# senseBox-RTC-RV8523_v20.net
KiCad netlist of a schematic drawn in EAGLE
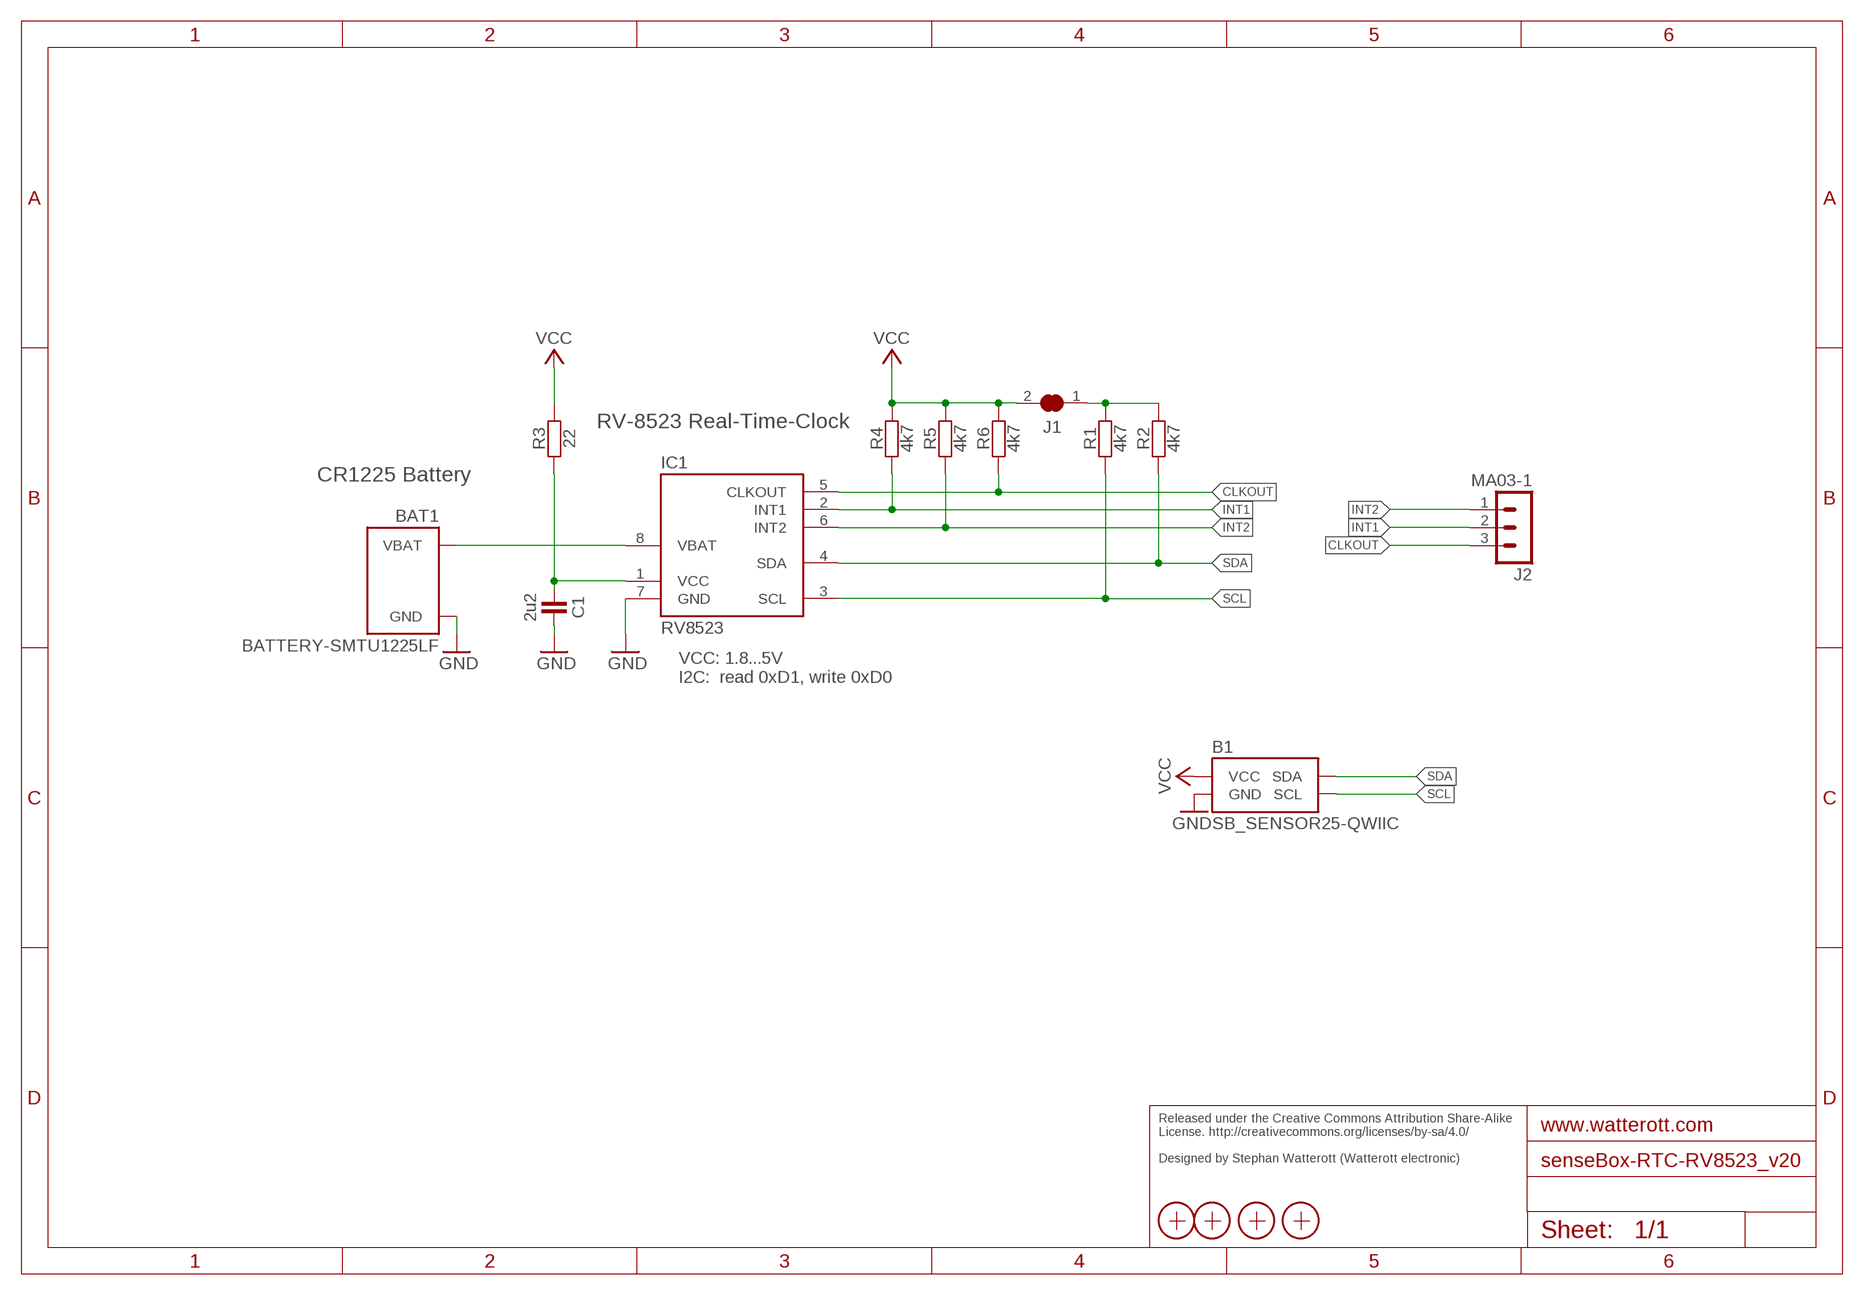
[diagram p0: schematic, sheet 1]

(export (version "E")
  (design (tool "Eeschema 10.0.6"))
  (components
    (comp (ref "B1")
      (value "SB_SENSOR25-QWIIC")
      (footprint "eagle-import:SB-25X25_QWIIC")
      (libsource (lib "eagle-import") (part "SB_SENSOR25-QWIIC"))
    )
    (comp (ref "BAT1")
      (value "BATTERY-SMTU1225LF")
      (footprint "eagle-import:BAT-SMTU1225LF")
      (libsource (lib "eagle-import") (part "BATTERY-SMTU1225LF"))
    )
    (comp (ref "C1")
      (value "2u2")
      (footprint "eagle-import:R0402")
      (libsource (lib "eagle-import") (part "CAPACITOR-C0402"))
    )
    (comp (ref "IC1")
      (value "RV8523")
      (footprint "eagle-import:RTC-C3")
      (libsource (lib "eagle-import") (part "RV8523-C3"))
    )
    (comp (ref "J1")
      (value "JUMPER2")
      (footprint "eagle-import:JUMPER2")
      (libsource (lib "eagle-import") (part "JUMPER2"))
    )
    (comp (ref "J2")
      (value "MA03-1")
      (footprint "eagle-import:MA03-1")
      (libsource (lib "eagle-import") (part "MA03-1"))
    )
    (comp (ref "R1")
      (value "4k7")
      (footprint "eagle-import:R0402")
      (libsource (lib "eagle-import") (part "RESISTOR-R0402"))
    )
    (comp (ref "R2")
      (value "4k7")
      (footprint "eagle-import:R0402")
      (libsource (lib "eagle-import") (part "RESISTOR-R0402"))
    )
    (comp (ref "R3")
      (value "22")
      (footprint "eagle-import:R0402")
      (libsource (lib "eagle-import") (part "RESISTOR-R0402"))
    )
    (comp (ref "R4")
      (value "4k7")
      (footprint "eagle-import:R0402")
      (libsource (lib "eagle-import") (part "RESISTOR-R0402"))
    )
    (comp (ref "R5")
      (value "4k7")
      (footprint "eagle-import:R0402")
      (libsource (lib "eagle-import") (part "RESISTOR-R0402"))
    )
    (comp (ref "R6")
      (value "4k7")
      (footprint "eagle-import:R0402")
      (libsource (lib "eagle-import") (part "RESISTOR-R0402"))
    )
    (comp (ref "X1")
      (value "PASSER-07")
      (footprint "eagle-import:PASSER_07MM")
      (libsource (lib "eagle-import") (part "PASSER-07"))
    )
    (comp (ref "X2")
      (value "PASSER-07")
      (footprint "eagle-import:PASSER_07MM")
      (libsource (lib "eagle-import") (part "PASSER-07"))
    )
    (comp (ref "X3")
      (value "PASSER-07")
      (footprint "eagle-import:PASSER_07MM")
      (libsource (lib "eagle-import") (part "PASSER-07"))
    )
    (comp (ref "X4")
      (value "PASSER-07")
      (footprint "eagle-import:PASSER_07MM")
      (libsource (lib "eagle-import") (part "PASSER-07"))
    )
  )
  (nets
    (net (code "1") (name "CLKOUT") (class "Default")
      (node (ref "IC1") (pin "5") (pinfunction "CLKOUT_5") (pintype "bidirectional"))
      (node (ref "J2") (pin "3") (pinfunction "3_3") (pintype "passive"))
      (node (ref "R6") (pin "1") (pinfunction "1_1") (pintype "passive"))
    )
    (net (code "2") (name "GND") (class "Default")
      (node (ref "B1") (pin "GND") (pinfunction "GND_GND") (pintype "power_in"))
      (node (ref "B1") (pin "GND1") (pinfunction "GND_GND1") (pintype "power_in"))
      (node (ref "B1") (pin "GND2") (pinfunction "GND_GND2") (pintype "power_in"))
      (node (ref "B1") (pin "SHLD1") (pinfunction "GND_SHLD1") (pintype "power_in"))
      (node (ref "B1") (pin "SHLD2") (pinfunction "GND_SHLD2") (pintype "power_in"))
      (node (ref "B1") (pin "SHLD3") (pinfunction "GND_SHLD3") (pintype "power_in"))
      (node (ref "B1") (pin "SHLD4") (pinfunction "GND_SHLD4") (pintype "power_in"))
      (node (ref "B1") (pin "SHLD5") (pinfunction "GND_SHLD5") (pintype "power_in"))
      (node (ref "B1") (pin "SHLD6") (pinfunction "GND_SHLD6") (pintype "power_in"))
      (node (ref "BAT1") (pin "-") (pinfunction "GND_-") (pintype "passive"))
      (node (ref "C1") (pin "2") (pinfunction "2_2") (pintype "passive"))
      (node (ref "IC1") (pin "7") (pinfunction "GND_7") (pintype "power_in"))
    )
    (net (code "3") (name "INT1") (class "Default")
      (node (ref "IC1") (pin "2") (pinfunction "INT1_2") (pintype "bidirectional"))
      (node (ref "J2") (pin "2") (pinfunction "2_2") (pintype "passive"))
      (node (ref "R4") (pin "1") (pinfunction "1_1") (pintype "passive"))
    )
    (net (code "4") (name "INT2") (class "Default")
      (node (ref "IC1") (pin "6") (pinfunction "INT2_6") (pintype "bidirectional"))
      (node (ref "J2") (pin "1") (pinfunction "1_1") (pintype "passive"))
      (node (ref "R5") (pin "1") (pinfunction "1_1") (pintype "passive"))
    )
    (net (code "5") (name "Net-(BAT1-VBAT)") (class "Default")
      (node (ref "BAT1") (pin "+") (pinfunction "VBAT_+") (pintype "passive"))
      (node (ref "IC1") (pin "8") (pinfunction "VBAT_8") (pintype "power_in"))
    )
    (net (code "6") (name "Net-(IC1-VCC)") (class "Default")
      (node (ref "C1") (pin "1") (pinfunction "1_1") (pintype "passive"))
      (node (ref "IC1") (pin "1") (pinfunction "VCC_1") (pintype "power_in"))
      (node (ref "R3") (pin "1") (pinfunction "1_1") (pintype "passive"))
    )
    (net (code "7") (name "Net-(J1-Pad1)") (class "Default")
      (node (ref "J1") (pin "1") (pinfunction "1_1") (pintype "passive"))
      (node (ref "R1") (pin "2") (pinfunction "2_2") (pintype "passive"))
      (node (ref "R2") (pin "2") (pinfunction "2_2") (pintype "passive"))
    )
    (net (code "8") (name "SCL") (class "Default")
      (node (ref "B1") (pin "SCL") (pinfunction "SCL_SCL") (pintype "bidirectional"))
      (node (ref "B1") (pin "SCL1") (pinfunction "SCL_SCL1") (pintype "bidirectional"))
      (node (ref "B1") (pin "SCL2") (pinfunction "SCL_SCL2") (pintype "bidirectional"))
      (node (ref "IC1") (pin "3") (pinfunction "SCL_3") (pintype "bidirectional"))
      (node (ref "R1") (pin "1") (pinfunction "1_1") (pintype "passive"))
    )
    (net (code "9") (name "SDA") (class "Default")
      (node (ref "B1") (pin "SDA") (pinfunction "SDA_SDA") (pintype "bidirectional"))
      (node (ref "B1") (pin "SDA1") (pinfunction "SDA_SDA1") (pintype "bidirectional"))
      (node (ref "B1") (pin "SDA2") (pinfunction "SDA_SDA2") (pintype "bidirectional"))
      (node (ref "IC1") (pin "4") (pinfunction "SDA_4") (pintype "bidirectional"))
      (node (ref "R2") (pin "1") (pinfunction "1_1") (pintype "passive"))
    )
    (net (code "10") (name "VCC") (class "Default")
      (node (ref "B1") (pin "VCC") (pinfunction "VCC_VCC") (pintype "power_in"))
      (node (ref "B1") (pin "VCC1") (pinfunction "VCC_VCC1") (pintype "power_in"))
      (node (ref "B1") (pin "VCC2") (pinfunction "VCC_VCC2") (pintype "power_in"))
      (node (ref "J1") (pin "2") (pinfunction "2_2") (pintype "passive"))
      (node (ref "R3") (pin "2") (pinfunction "2_2") (pintype "passive"))
      (node (ref "R4") (pin "2") (pinfunction "2_2") (pintype "passive"))
      (node (ref "R5") (pin "2") (pinfunction "2_2") (pintype "passive"))
      (node (ref "R6") (pin "2") (pinfunction "2_2") (pintype "passive"))
    )
  )
)
